# GZ7_1_x-ALARM.net
KiCad netlist of a schematic drawn in Altium Designer
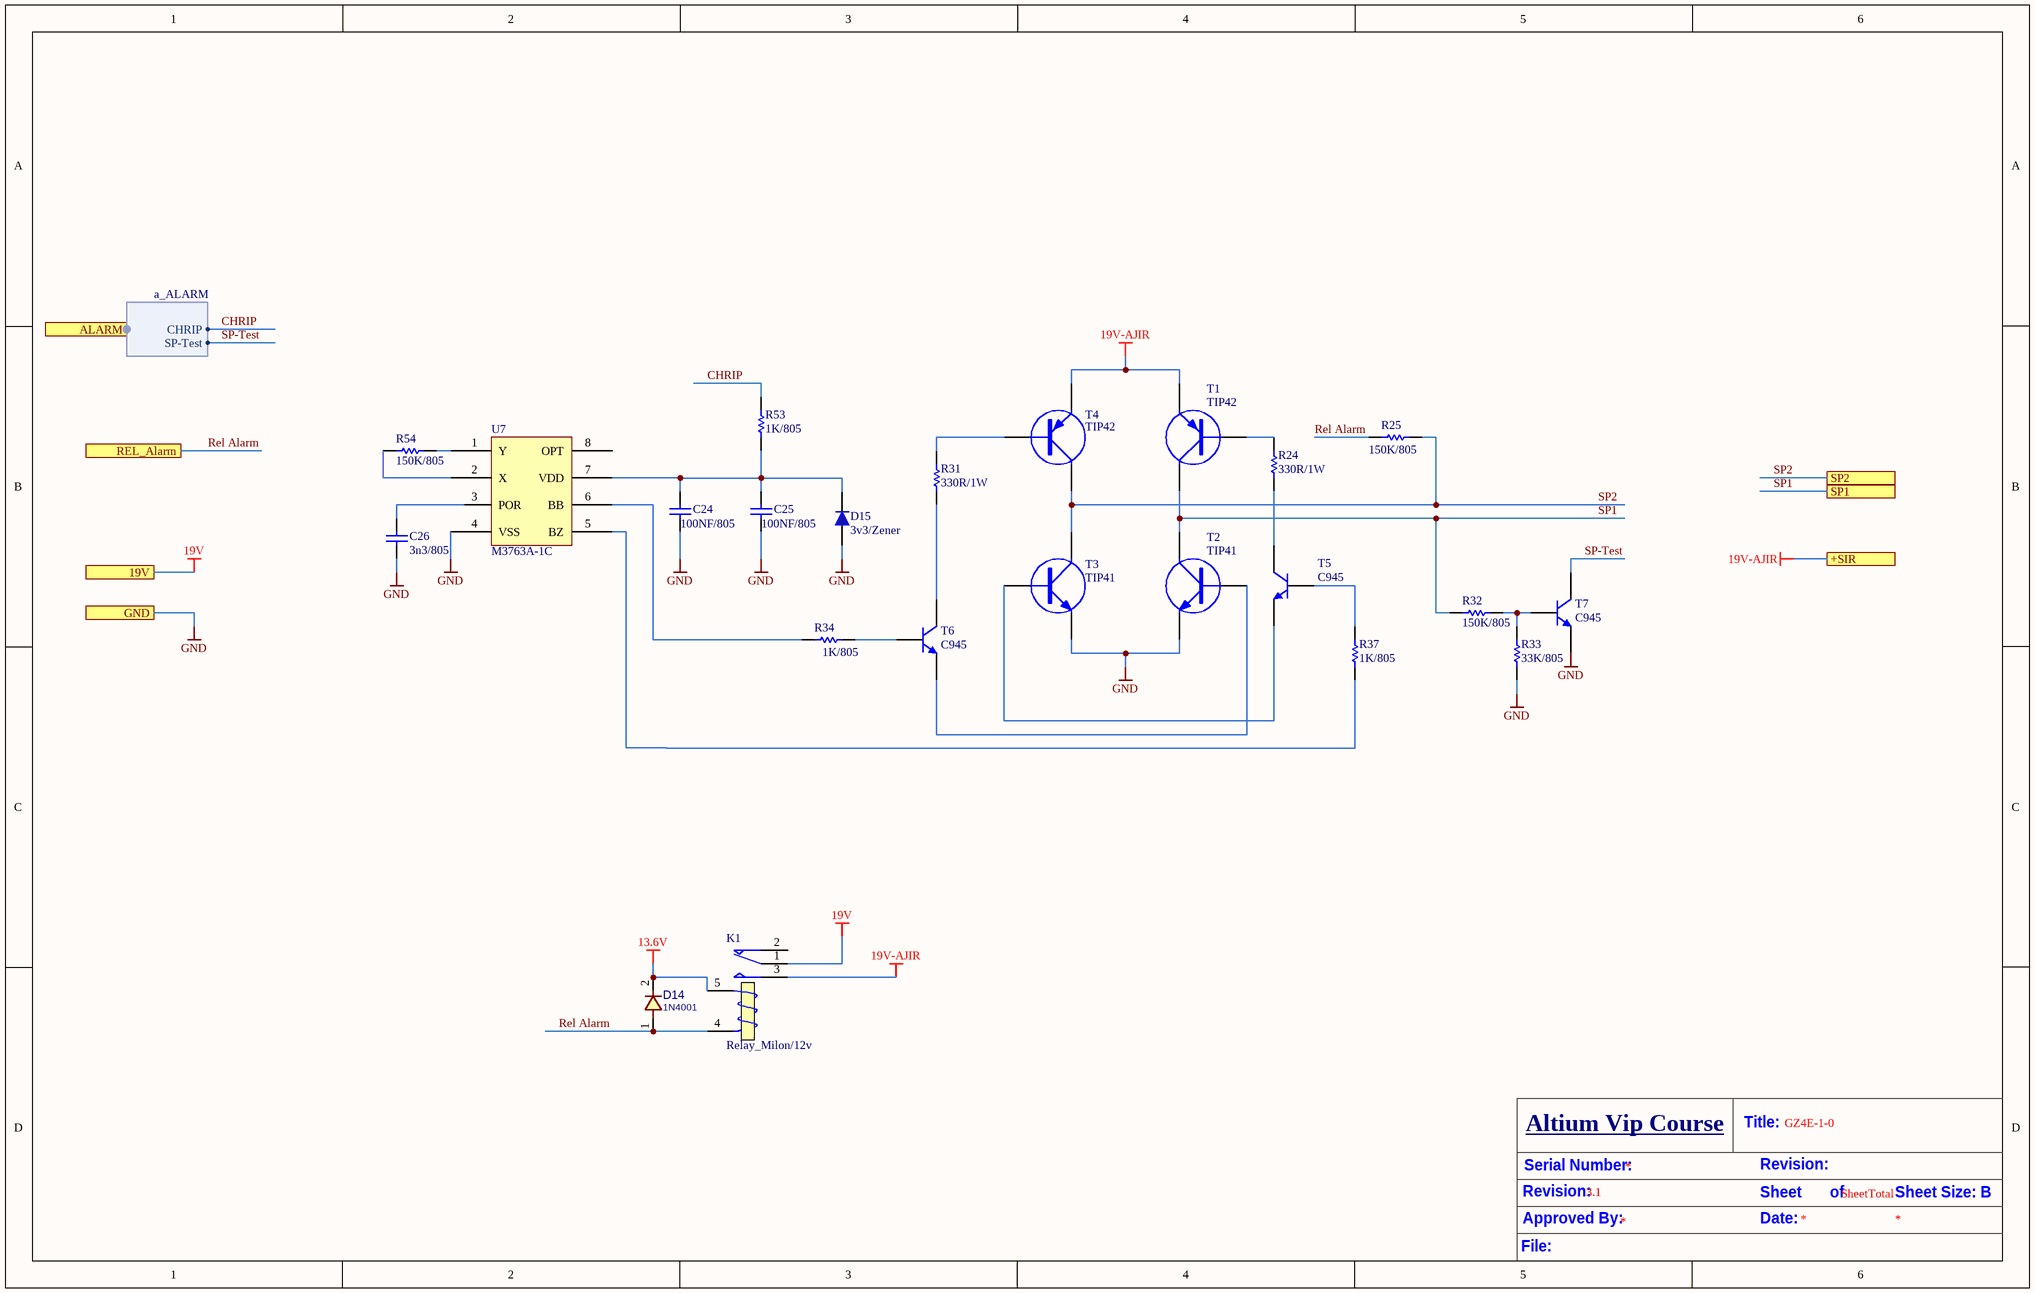
[diagram p0: GZ7_1_x-ALARM.SchDoc]

(export (version "E")
  (design (tool "Eeschema 10.0.6"))
  (components
    (comp (ref "C24")
      (value "100NF/805")
      (footprint "MY805 COP")
      (description "CAP 0805")
      (fields (field (name "DESIGNER") "Abbas Basereh"))
      (libsource (lib "Altium") (part "CAP SMD 0805"))
    )
    (comp (ref "C25")
      (value "100NF/805")
      (footprint "MY805 COP")
      (description "CAP 0805")
      (fields (field (name "DESIGNER") "Abbas Basereh"))
      (libsource (lib "Altium") (part "CAP SMD 0805"))
    )
    (comp (ref "C26")
      (value "3n3/805")
      (footprint "MY805 COP")
      (description "CAP 0805")
      (fields (field (name "DESIGNER") "Abbas Basereh"))
      (libsource (lib "Altium") (part "CAP SMD 0805"))
    )
    (comp (ref "D14")
      (value "1N4001")
      (footprint "DIODE 1N4007 SMD")
      (description "DIODE, THD")
      (fields (field (name "MANF") "MANF"))
      (libsource (lib "diode") (part "DIODE_THD"))
    )
    (comp (ref "D15")
      (value "3v3/Zener")
      (footprint "my-DO5X.1.5")
      (description "Zener")
      (libsource (lib "Altium") (part "1N4148 SMD"))
    )
    (comp (ref "K1")
      (value "Relay_Milon/12v")
      (footprint "REL")
      (description "Relay_Milon")
      (fields (field (name "DESIGNER") "Ali Hafizi"))
      (libsource (lib "Altium") (part "RELAY General"))
    )
    (comp (ref "R24")
      (value "330R/1W")
      (footprint "R2512")
      (description "RES Axial 1W")
      (fields (field (name "DESIGNER") "Abbas Basereh"))
      (libsource (lib "Altium") (part "RES Axial 1W"))
    )
    (comp (ref "R25")
      (value "150K/805")
      (footprint "my805")
      (description "RES 805")
      (fields (field (name "DESIGNER") "Abbas Basereh"))
      (libsource (lib "Altium") (part "RES Axial 1W"))
    )
    (comp (ref "R31")
      (value "330R/1W")
      (footprint "R2512")
      (description "RES Axial 1W")
      (fields (field (name "DESIGNER") "Abbas Basereh"))
      (libsource (lib "Altium") (part "RES Axial 1W"))
    )
    (comp (ref "R32")
      (value "150K/805")
      (footprint "my805")
      (description "RES 805")
      (fields (field (name "DESIGNER") "Abbas Basereh"))
      (libsource (lib "Altium") (part "RES Axial 1W"))
    )
    (comp (ref "R33")
      (value "33K/805")
      (footprint "my805")
      (description "RES 805")
      (fields (field (name "DESIGNER") "Abbas Basereh"))
      (libsource (lib "Altium") (part "RES Axial 1W"))
    )
    (comp (ref "R34")
      (value "1K/805")
      (footprint "my805")
      (description "RES 805")
      (fields (field (name "DESIGNER") "Abbas Basereh"))
      (libsource (lib "Altium") (part "RES 1206 0.25W"))
    )
    (comp (ref "R37")
      (value "1K/805")
      (footprint "my805")
      (description "RES 805")
      (fields (field (name "DESIGNER") "Abbas Basereh"))
      (libsource (lib "Altium") (part "RES 1206 0.25W"))
    )
    (comp (ref "R53")
      (value "1K/805")
      (footprint "my805")
      (description "RES 805")
      (fields (field (name "DESIGNER") "Abbas Basereh"))
      (libsource (lib "Altium") (part "RES 1206 0.25W"))
    )
    (comp (ref "R54")
      (value "150K/805")
      (footprint "my805")
      (description "RES 805")
      (fields (field (name "DESIGNER") "Abbas Basereh"))
      (libsource (lib "Altium") (part "RES 1206 0.25W"))
    )
    (comp (ref "T1")
      (value "TIP42")
      (footprint "TO-220 AB")
      (description "PNP Transistor")
      (libsource (lib "*") (part "PNP"))
    )
    (comp (ref "T2")
      (value "TIP41")
      (footprint "TO-220 AB")
      (description "NPN Transistor")
      (libsource (lib "*") (part "NPN"))
    )
    (comp (ref "T3")
      (value "TIP41")
      (footprint "TO-220 AB")
      (description "NPN Transistor")
      (libsource (lib "*") (part "NPN"))
    )
    (comp (ref "T4")
      (value "TIP42")
      (footprint "TO-220 AB")
      (description "PNP Transistor")
      (libsource (lib "*") (part "PNP"))
    )
    (comp (ref "T5")
      (value "C945")
      (footprint "SOT23_N")
      (description "NPN Transistor")
      (fields (field (name "PUBLISHER") "Abbas Basereh"))
      (libsource (lib "Altium") (part "C945"))
    )
    (comp (ref "T6")
      (value "C945")
      (footprint "SOT23_N")
      (description "NPN Transistor")
      (fields (field (name "PUBLISHER") "Abbas Basereh"))
      (libsource (lib "Altium") (part "C945"))
    )
    (comp (ref "T7")
      (value "C945")
      (footprint "SOT23_N")
      (description "NPN Transistor")
      (fields (field (name "PUBLISHER") "Abbas Basereh"))
      (libsource (lib "Altium") (part "C945"))
    )
    (comp (ref "U7") (value "M3763A-1C") (footprint "DIP8") (libsource (lib "GZ8_4_0") (part "M3763A-1C")))
  )
  (nets
    (net (code "2") (name "/CHRIP") (class "Default")
      (node (ref "R53") (pin "2") (pinfunction "2_2") (pintype "passive"))
    )
    (net (code "3") (name "/Rel Alarm") (class "Default")
      (node (ref "D14") (pin "1") (pinfunction "1_1") (pintype "passive"))
      (node (ref "K1") (pin "4") (pinfunction "T1_4") (pintype "passive"))
      (node (ref "R25") (pin "1") (pinfunction "1_1") (pintype "passive"))
    )
    (net (code "4") (name "/SP-Test") (class "Default")
      (node (ref "T7") (pin "3") (pinfunction "C_3") (pintype "passive"))
    )
    (net (code "5") (name "/SP1") (class "Default")
      (node (ref "R32") (pin "1") (pinfunction "1_1") (pintype "passive"))
      (node (ref "T1") (pin "2") (pinfunction "E_2") (pintype "passive"))
      (node (ref "T2") (pin "2") (pinfunction "C_2") (pintype "passive"))
    )
    (net (code "6") (name "/SP2") (class "Default")
      (node (ref "R25") (pin "2") (pinfunction "2_2") (pintype "passive"))
      (node (ref "T3") (pin "2") (pinfunction "C_2") (pintype "passive"))
      (node (ref "T4") (pin "2") (pinfunction "E_2") (pintype "passive"))
    )
    (net (code "8") (name "13.6V") (class "Default")
      (node (ref "D14") (pin "2") (pinfunction "2_2") (pintype "passive"))
      (node (ref "K1") (pin "5") (pinfunction "T2_5") (pintype "passive"))
    )
    (net (code "9") (name "19V") (class "Default")
      (node (ref "K1") (pin "1") (pinfunction "COM_1") (pintype "passive"))
    )
    (net (code "10") (name "19V-AJIR") (class "Default")
      (node (ref "K1") (pin "3") (pinfunction "NO_3") (pintype "passive"))
      (node (ref "T1") (pin "3") (pinfunction "C_3") (pintype "passive"))
      (node (ref "T4") (pin "3") (pinfunction "C_3") (pintype "passive"))
    )
    (net (code "11") (name "GND") (class "Default")
      (node (ref "C24") (pin "1") (pinfunction "1_1") (pintype "passive"))
      (node (ref "C25") (pin "1") (pinfunction "1_1") (pintype "passive"))
      (node (ref "C26") (pin "1") (pinfunction "1_1") (pintype "passive"))
      (node (ref "D15") (pin "1") (pintype "passive"))
      (node (ref "R33") (pin "2") (pinfunction "2_2") (pintype "passive"))
      (node (ref "T2") (pin "3") (pinfunction "E_3") (pintype "passive"))
      (node (ref "T3") (pin "3") (pinfunction "E_3") (pintype "passive"))
      (node (ref "T7") (pin "2") (pinfunction "E_2") (pintype "passive"))
      (node (ref "U7") (pin "4") (pinfunction "VSS_4") (pintype "passive"))
    )
    (net (code "12") (name "Net-(T1-B)") (class "Default")
      (node (ref "R24") (pin "2") (pinfunction "2_2") (pintype "passive"))
      (node (ref "T1") (pin "1") (pinfunction "B_1") (pintype "passive"))
    )
    (net (code "13") (name "Net-(T2-B)") (class "Default")
      (node (ref "T2") (pin "1") (pinfunction "B_1") (pintype "passive"))
      (node (ref "T6") (pin "2") (pinfunction "E_2") (pintype "passive"))
    )
    (net (code "14") (name "Net-(T3-B)") (class "Default")
      (node (ref "T3") (pin "1") (pinfunction "B_1") (pintype "passive"))
      (node (ref "T5") (pin "2") (pinfunction "E_2") (pintype "passive"))
    )
    (net (code "15") (name "Net-(T4-B)") (class "Default")
      (node (ref "R31") (pin "2") (pinfunction "2_2") (pintype "passive"))
      (node (ref "T4") (pin "1") (pinfunction "B_1") (pintype "passive"))
    )
    (net (code "16") (name "Net-(T5-B)") (class "Default")
      (node (ref "R37") (pin "2") (pinfunction "2_2") (pintype "passive"))
      (node (ref "T5") (pin "1") (pinfunction "B_1") (pintype "passive"))
    )
    (net (code "17") (name "Net-(T5-C)") (class "Default")
      (node (ref "R24") (pin "1") (pinfunction "1_1") (pintype "passive"))
      (node (ref "T5") (pin "3") (pinfunction "C_3") (pintype "passive"))
    )
    (net (code "18") (name "Net-(T6-B)") (class "Default")
      (node (ref "R34") (pin "1") (pinfunction "1_1") (pintype "passive"))
      (node (ref "T6") (pin "1") (pinfunction "B_1") (pintype "passive"))
    )
    (net (code "19") (name "Net-(T6-C)") (class "Default")
      (node (ref "R31") (pin "1") (pinfunction "1_1") (pintype "passive"))
      (node (ref "T6") (pin "3") (pinfunction "C_3") (pintype "passive"))
    )
    (net (code "20") (name "Net-(T7-B)") (class "Default")
      (node (ref "R32") (pin "2") (pinfunction "2_2") (pintype "passive"))
      (node (ref "R33") (pin "1") (pinfunction "1_1") (pintype "passive"))
      (node (ref "T7") (pin "1") (pinfunction "B_1") (pintype "passive"))
    )
    (net (code "21") (name "Net-(U7-BB)") (class "Default")
      (node (ref "R34") (pin "2") (pinfunction "2_2") (pintype "passive"))
      (node (ref "U7") (pin "6") (pinfunction "BB_6") (pintype "passive"))
    )
    (net (code "22") (name "Net-(U7-BZ)") (class "Default")
      (node (ref "R37") (pin "1") (pinfunction "1_1") (pintype "passive"))
      (node (ref "U7") (pin "5") (pinfunction "BZ_5") (pintype "passive"))
    )
    (net (code "23") (name "Net-(U7-POR)") (class "Default")
      (node (ref "C26") (pin "2") (pinfunction "2_2") (pintype "passive"))
      (node (ref "U7") (pin "3") (pinfunction "POR_3") (pintype "passive"))
    )
    (net (code "24") (name "Net-(U7-VDD)") (class "Default")
      (node (ref "C24") (pin "2") (pinfunction "2_2") (pintype "passive"))
      (node (ref "C25") (pin "2") (pinfunction "2_2") (pintype "passive"))
      (node (ref "D15") (pin "2") (pintype "passive"))
      (node (ref "R53") (pin "1") (pinfunction "1_1") (pintype "passive"))
      (node (ref "U7") (pin "7") (pinfunction "VDD_7") (pintype "passive"))
    )
    (net (code "25") (name "Net-(U7-X)") (class "Default")
      (node (ref "R54") (pin "1") (pinfunction "1_1") (pintype "passive"))
      (node (ref "U7") (pin "2") (pinfunction "X_2") (pintype "passive"))
    )
    (net (code "26") (name "Net-(U7-Y)") (class "Default")
      (node (ref "R54") (pin "2") (pinfunction "2_2") (pintype "passive"))
      (node (ref "U7") (pin "1") (pinfunction "Y_1") (pintype "passive"))
    )
    (net (code "27") (name "unconnected-(K1-NC-Pad2)") (class "Default")
      (node (ref "K1") (pin "2") (pinfunction "NC_2") (pintype "passive"))
    )
    (net (code "28") (name "unconnected-(U7-OPT-Pad8)") (class "Default")
      (node (ref "U7") (pin "8") (pinfunction "OPT_8") (pintype "passive"))
    )
  )
)
